# Pure_ADSR.net
KiCad netlist of a schematic drawn in EAGLE
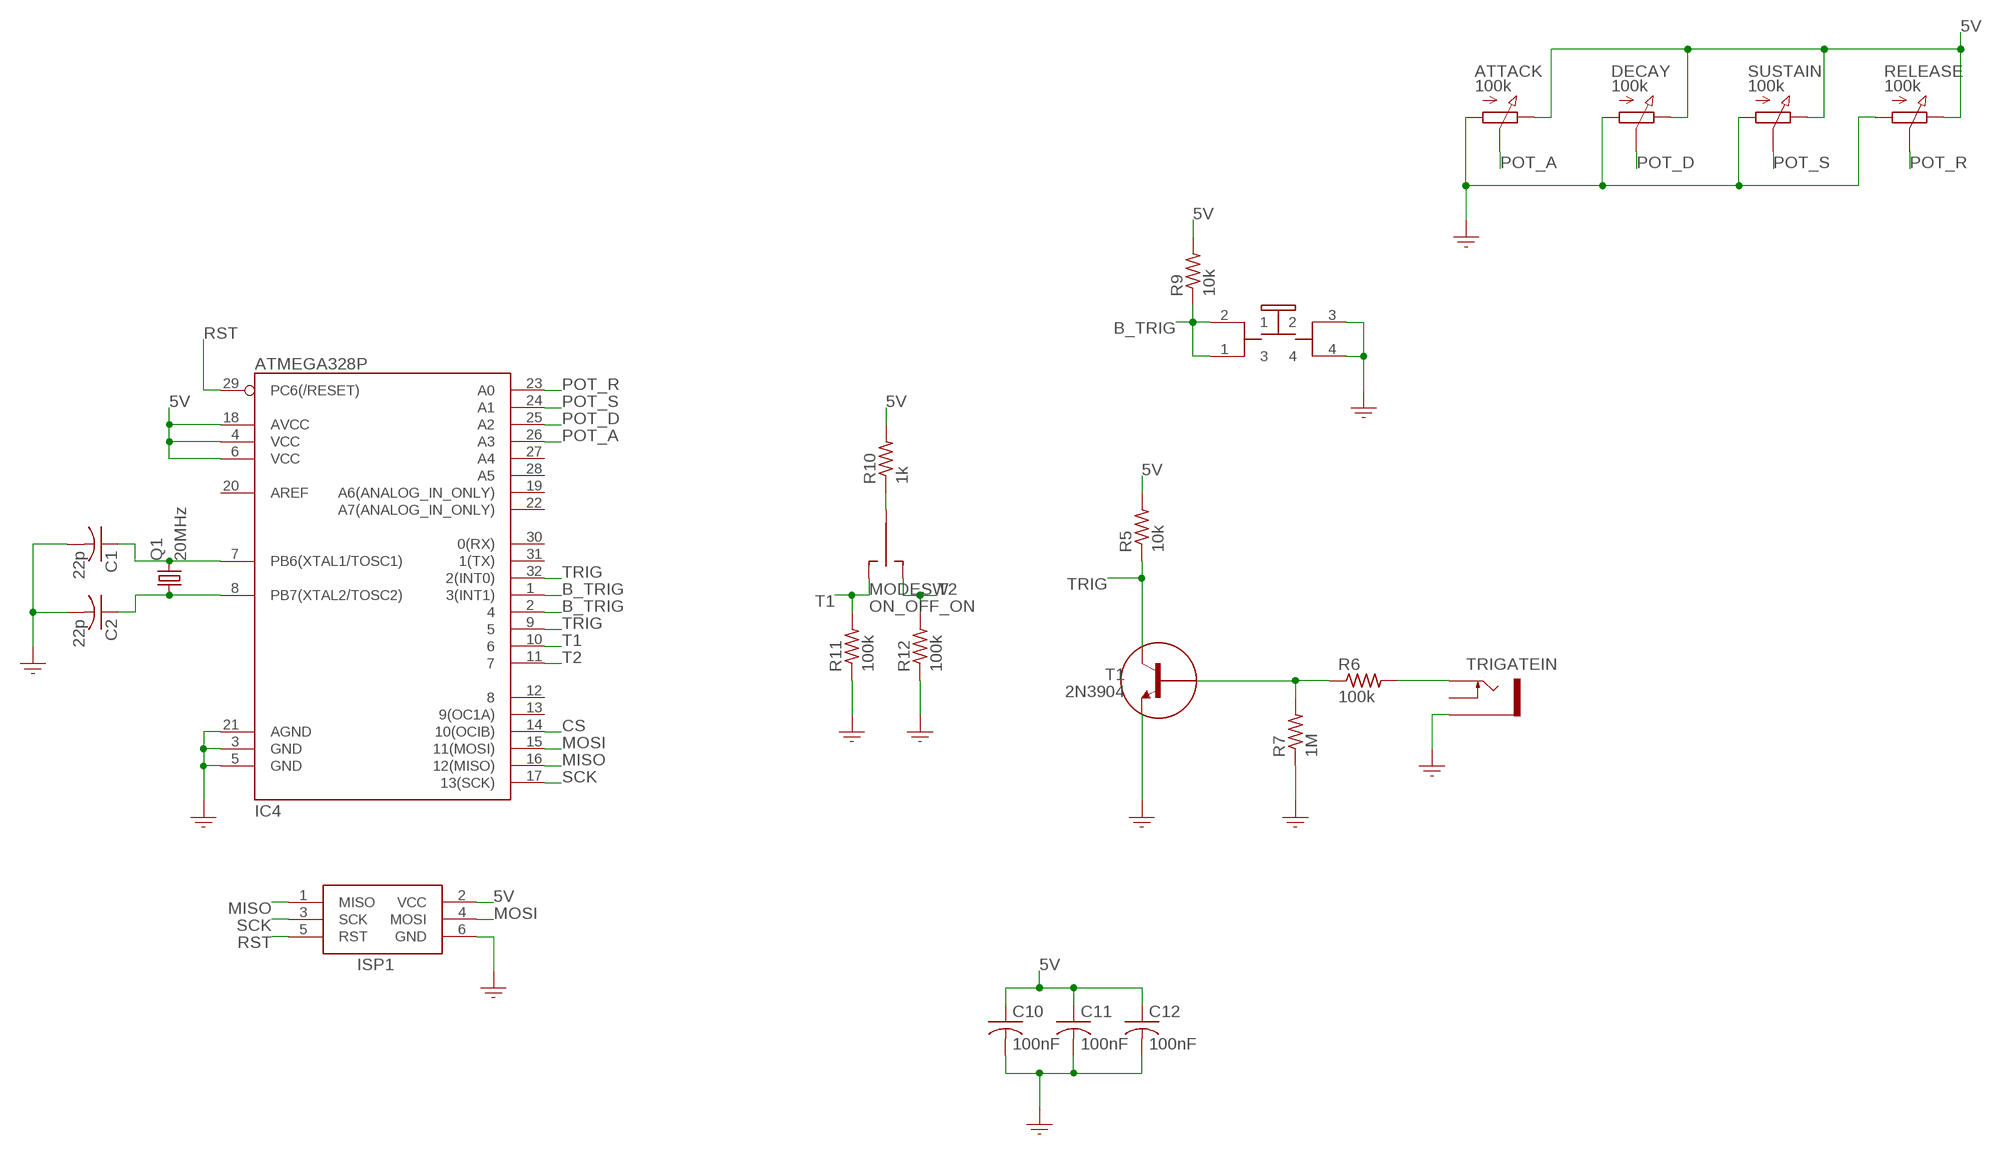
[diagram p0: schematic, sheet 1]
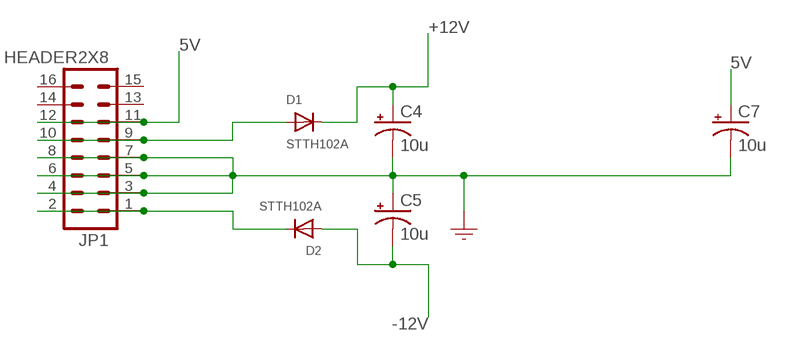
[diagram p1: schematic, sheet 2]
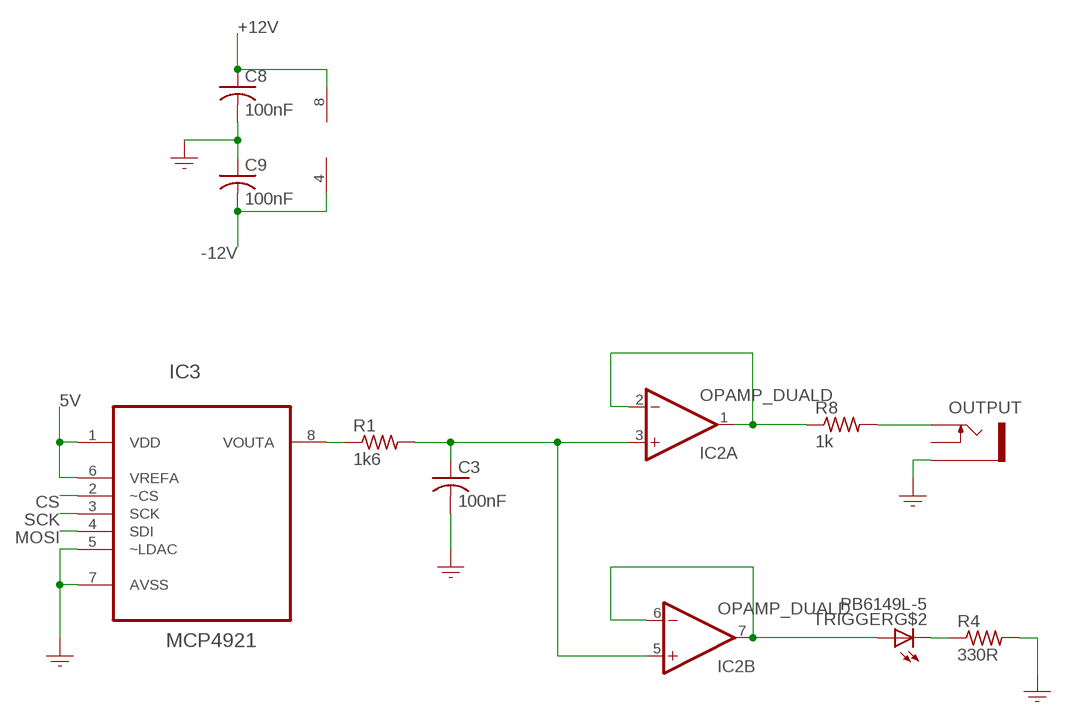
[diagram p2: schematic, sheet 3]

(export (version "E")
  (design (tool "Eeschema 10.0.6"))
  (components
    (comp (ref "ATTACK")
      (value "100k")
      (footprint "eagle-import:POTENTIOMETER_9MM")
      (libsource (lib "eagle-import") (part "RESISTOR_VARIABLE9MM_POT"))
    )
    (comp (ref "C1")
      (value "22p")
      (footprint "eagle-import:C0805")
      (libsource (lib "eagle-import") (part "CAPACITOR-USC0805"))
    )
    (comp (ref "C2")
      (value "22p")
      (footprint "eagle-import:C0805")
      (libsource (lib "eagle-import") (part "CAPACITOR-USC0805"))
    )
    (comp (ref "C10")
      (value "100nF")
      (footprint "eagle-import:C0805")
      (libsource (lib "eagle-import") (part "CAPACITOR-USC0805"))
    )
    (comp (ref "C11")
      (value "100nF")
      (footprint "eagle-import:C0805")
      (libsource (lib "eagle-import") (part "CAPACITOR-USC0805"))
    )
    (comp (ref "C12")
      (value "100nF")
      (footprint "eagle-import:C0805")
      (libsource (lib "eagle-import") (part "CAPACITOR-USC0805"))
    )
    (comp (ref "DECAY")
      (value "100k")
      (footprint "eagle-import:POTENTIOMETER_9MM")
      (libsource (lib "eagle-import") (part "RESISTOR_VARIABLE9MM_POT"))
    )
    (comp (ref "IC4")
      (value "ATMEGA328P")
      (footprint "eagle-import:TQFP32-08")
      (libsource (lib "eagle-import") (part "MICROPROCESSOR_ATMEGA328_SMT"))
    )
    (comp (ref "ISP1")
      (value "HEADER2X3-6")
      (footprint "eagle-import:AVRISP")
      (libsource (lib "eagle-import") (part "HEADER2X3-6"))
    )
    (comp (ref "MODESW")
      (value "ON_OFF_ON")
      (footprint "eagle-import:TOGGLE_SW")
      (libsource (lib "eagle-import") (part "SWITCH_TOGGLE_SPDT"))
    )
    (comp (ref "Q1")
      (value "20MHz")
      (footprint "eagle-import:HC49UP")
      (libsource (lib "eagle-import") (part "CRYSTALHC49UP"))
    )
    (comp (ref "R5")
      (value "10k")
      (footprint "eagle-import:R0805")
      (libsource (lib "eagle-import") (part "RESISTOR_USR0805"))
    )
    (comp (ref "R6")
      (value "100k")
      (footprint "eagle-import:R0805")
      (libsource (lib "eagle-import") (part "RESISTOR_USR0805"))
    )
    (comp (ref "R7")
      (value "1M")
      (footprint "eagle-import:R0805")
      (libsource (lib "eagle-import") (part "RESISTOR_USR0805"))
    )
    (comp (ref "R9")
      (value "10k")
      (footprint "eagle-import:R0805")
      (libsource (lib "eagle-import") (part "RESISTOR_USR0805"))
    )
    (comp (ref "R10")
      (value "1k")
      (footprint "eagle-import:R0805")
      (libsource (lib "eagle-import") (part "RESISTOR_USR0805"))
    )
    (comp (ref "R11")
      (value "100k")
      (footprint "eagle-import:R0805")
      (libsource (lib "eagle-import") (part "RESISTOR_USR0805"))
    )
    (comp (ref "R12")
      (value "100k")
      (footprint "eagle-import:R0805")
      (libsource (lib "eagle-import") (part "RESISTOR_USR0805"))
    )
    (comp (ref "RELEASE")
      (value "100k")
      (footprint "eagle-import:POTENTIOMETER_9MM")
      (libsource (lib "eagle-import") (part "RESISTOR_VARIABLE9MM_POT"))
    )
    (comp (ref "SUSTAIN")
      (value "100k")
      (footprint "eagle-import:POTENTIOMETER_9MM")
      (libsource (lib "eagle-import") (part "RESISTOR_VARIABLE9MM_POT"))
    )
    (comp (ref "T1")
      (value "2N3904")
      (footprint "eagle-import:SOT23")
      (libsource (lib "eagle-import") (part "TRANSISTOR_NPNMMBT2222A"))
    )
    (comp (ref "TRIGATEIN")
      (value "SOCKET_MONO_3.5MMPJ301M-12")
      (footprint "eagle-import:PJ301M-12")
      (libsource (lib "eagle-import") (part "SOCKET_MONO_3.5MMPJ301M-12"))
    )
    (comp (ref "TRIGGER")
      (value "PB6149L-5")
      (footprint "eagle-import:PB6149L")
      (libsource (lib "eagle-import") (part "SWITCH_PUSHBUTTON_LED"))
    )
    (comp (ref "C4")
      (value "10u")
      (footprint "eagle-import:153CLV-0505")
      (libsource (lib "eagle-import") (part "CAPACITOR_POL-US153CLV-0505"))
    )
    (comp (ref "C5")
      (value "10u")
      (footprint "eagle-import:153CLV-0505")
      (libsource (lib "eagle-import") (part "CAPACITOR_POL-US153CLV-0505"))
    )
    (comp (ref "C7")
      (value "10u")
      (footprint "eagle-import:153CLV-0505")
      (libsource (lib "eagle-import") (part "CAPACITOR_POL-US153CLV-0505"))
    )
    (comp (ref "D1")
      (value "STTH102A")
      (footprint "eagle-import:SMADIODE")
      (libsource (lib "eagle-import") (part "DIODESMA"))
    )
    (comp (ref "D2")
      (value "STTH102A")
      (footprint "eagle-import:SMADIODE")
      (libsource (lib "eagle-import") (part "DIODESMA"))
    )
    (comp (ref "JP1")
      (value "HEADER2X8")
      (footprint "eagle-import:POWER_SHROUDED")
      (libsource (lib "eagle-import") (part "HEADER2X8"))
    )
    (comp (ref "C3")
      (value "100nF")
      (footprint "eagle-import:C0805")
      (libsource (lib "eagle-import") (part "CAPACITOR-USC0805"))
    )
    (comp (ref "C8")
      (value "100nF")
      (footprint "eagle-import:C0805")
      (libsource (lib "eagle-import") (part "CAPACITOR-USC0805"))
    )
    (comp (ref "C9")
      (value "100nF")
      (footprint "eagle-import:C0805")
      (libsource (lib "eagle-import") (part "CAPACITOR-USC0805"))
    )
    (comp (ref "IC2")
      (value "OPAMP_DUALD")
      (footprint "eagle-import:SO08")
      (libsource (lib "eagle-import") (part "OPAMP_DUALD"))
    )
    (comp (ref "IC3")
      (value "MCP4921")
      (footprint "eagle-import:SOIC8")
      (libsource (lib "eagle-import") (part "DAC_SINGLE_12B_MCP4921"))
    )
    (comp (ref "OUTPUT")
      (value "SOCKET_MONO_3.5MMPJ301M-12")
      (footprint "eagle-import:PJ301M-12")
      (libsource (lib "eagle-import") (part "SOCKET_MONO_3.5MMPJ301M-12"))
    )
    (comp (ref "R1")
      (value "1k6")
      (footprint "eagle-import:R0805")
      (libsource (lib "eagle-import") (part "RESISTOR_USR0805"))
    )
    (comp (ref "R4")
      (value "330R")
      (footprint "eagle-import:R0805")
      (libsource (lib "eagle-import") (part "RESISTOR_USR0805"))
    )
    (comp (ref "R8")
      (value "1k")
      (footprint "eagle-import:R0805")
      (libsource (lib "eagle-import") (part "RESISTOR_USR0805"))
    )
  )
  (nets
    (net (code "1") (name "+12V") (class "Default")
      (node (ref "C4") (pin "+") (pinfunction "+_+") (pintype "passive"))
      (node (ref "C8") (pin "1") (pinfunction "1_1") (pintype "passive"))
      (node (ref "D1") (pin "C") (pinfunction "C_C") (pintype "passive"))
      (node (ref "IC2") (pin "8") (pinfunction "V+_8") (pintype "power_in"))
    )
    (net (code "2") (name "-12V") (class "Default")
      (node (ref "C5") (pin "-") (pinfunction "-_-") (pintype "passive"))
      (node (ref "C9") (pin "2") (pinfunction "2_2") (pintype "passive"))
      (node (ref "D2") (pin "A") (pinfunction "A_A") (pintype "passive"))
      (node (ref "IC2") (pin "4") (pinfunction "V-_4") (pintype "power_in"))
    )
    (net (code "3") (name "5V") (class "Default")
      (node (ref "ATTACK") (pin "P$3") (pinfunction "3_P$3") (pintype "passive"))
      (node (ref "C10") (pin "1") (pinfunction "1_1") (pintype "passive"))
      (node (ref "C11") (pin "1") (pinfunction "1_1") (pintype "passive"))
      (node (ref "C12") (pin "1") (pinfunction "1_1") (pintype "passive"))
      (node (ref "C7") (pin "+") (pinfunction "+_+") (pintype "passive"))
      (node (ref "DECAY") (pin "P$3") (pinfunction "3_P$3") (pintype "passive"))
      (node (ref "IC3") (pin "1") (pinfunction "VDD_1") (pintype "power_in"))
      (node (ref "IC3") (pin "6") (pinfunction "VREFA_6") (pintype "input"))
      (node (ref "IC4") (pin "18") (pinfunction "AVCC_18") (pintype "bidirectional"))
      (node (ref "IC4") (pin "4") (pinfunction "VCC_4") (pintype "bidirectional"))
      (node (ref "IC4") (pin "6") (pinfunction "VCC_6") (pintype "bidirectional"))
      (node (ref "ISP1") (pin "2") (pinfunction "VCC_2") (pintype "power_in"))
      (node (ref "JP1") (pin "11") (pinfunction "11_11") (pintype "passive"))
      (node (ref "JP1") (pin "12") (pinfunction "12_12") (pintype "passive"))
      (node (ref "R10") (pin "2") (pinfunction "2_2") (pintype "passive"))
      (node (ref "R5") (pin "2") (pinfunction "2_2") (pintype "passive"))
      (node (ref "R9") (pin "2") (pinfunction "2_2") (pintype "passive"))
      (node (ref "RELEASE") (pin "P$3") (pinfunction "3_P$3") (pintype "passive"))
      (node (ref "SUSTAIN") (pin "P$3") (pinfunction "3_P$3") (pintype "passive"))
    )
    (net (code "4") (name "B_TRIG") (class "Default")
      (node (ref "IC4") (pin "1") (pinfunction "3(INT1)_1") (pintype "bidirectional"))
      (node (ref "IC4") (pin "2") (pinfunction "4_2") (pintype "bidirectional"))
      (node (ref "R9") (pin "1") (pinfunction "1_1") (pintype "passive"))
      (node (ref "TRIGGER") (pin "1") (pinfunction "3_1") (pintype "bidirectional"))
      (node (ref "TRIGGER") (pin "2") (pinfunction "1_2") (pintype "bidirectional"))
    )
    (net (code "5") (name "CS") (class "Default")
      (node (ref "IC3") (pin "2") (pinfunction "~{CS}_2") (pintype "input"))
      (node (ref "IC4") (pin "14") (pinfunction "10(OCIB)_14") (pintype "bidirectional"))
    )
    (net (code "6") (name "GND") (class "Default")
      (node (ref "ATTACK") (pin "P$1") (pinfunction "1_P$1") (pintype "passive"))
      (node (ref "C1") (pin "2") (pinfunction "2_2") (pintype "passive"))
      (node (ref "C10") (pin "2") (pinfunction "2_2") (pintype "passive"))
      (node (ref "C11") (pin "2") (pinfunction "2_2") (pintype "passive"))
      (node (ref "C12") (pin "2") (pinfunction "2_2") (pintype "passive"))
      (node (ref "C2") (pin "2") (pinfunction "2_2") (pintype "passive"))
      (node (ref "C3") (pin "2") (pinfunction "2_2") (pintype "passive"))
      (node (ref "C4") (pin "-") (pinfunction "-_-") (pintype "passive"))
      (node (ref "C5") (pin "+") (pinfunction "+_+") (pintype "passive"))
      (node (ref "C7") (pin "-") (pinfunction "-_-") (pintype "passive"))
      (node (ref "C8") (pin "2") (pinfunction "2_2") (pintype "passive"))
      (node (ref "C9") (pin "1") (pinfunction "1_1") (pintype "passive"))
      (node (ref "DECAY") (pin "P$1") (pinfunction "1_P$1") (pintype "passive"))
      (node (ref "IC3") (pin "5") (pinfunction "~{LDAC}_5") (pintype "input"))
      (node (ref "IC3") (pin "7") (pinfunction "AVSS_7") (pintype "passive"))
      (node (ref "IC4") (pin "21") (pinfunction "AGND_21") (pintype "bidirectional"))
      (node (ref "IC4") (pin "3") (pinfunction "GND_3") (pintype "bidirectional"))
      (node (ref "IC4") (pin "5") (pinfunction "GND_5") (pintype "bidirectional"))
      (node (ref "ISP1") (pin "6") (pinfunction "GND_6") (pintype "power_in"))
      (node (ref "JP1") (pin "3") (pinfunction "3_3") (pintype "passive"))
      (node (ref "JP1") (pin "4") (pinfunction "4_4") (pintype "passive"))
      (node (ref "JP1") (pin "5") (pinfunction "5_5") (pintype "passive"))
      (node (ref "JP1") (pin "6") (pinfunction "6_6") (pintype "passive"))
      (node (ref "JP1") (pin "7") (pinfunction "7_7") (pintype "passive"))
      (node (ref "JP1") (pin "8") (pinfunction "8_8") (pintype "passive"))
      (node (ref "OUTPUT") (pin "GND") (pinfunction "SLEEVE_GND") (pintype "passive"))
      (node (ref "R11") (pin "1") (pinfunction "1_1") (pintype "passive"))
      (node (ref "R12") (pin "1") (pinfunction "1_1") (pintype "passive"))
      (node (ref "R4") (pin "2") (pinfunction "2_2") (pintype "passive"))
      (node (ref "R7") (pin "1") (pinfunction "1_1") (pintype "passive"))
      (node (ref "RELEASE") (pin "P$1") (pinfunction "1_P$1") (pintype "passive"))
      (node (ref "SUSTAIN") (pin "P$1") (pinfunction "1_P$1") (pintype "passive"))
      (node (ref "T1") (pin "2") (pinfunction "E_2") (pintype "passive"))
      (node (ref "TRIGATEIN") (pin "GND") (pinfunction "SLEEVE_GND") (pintype "passive"))
      (node (ref "TRIGGER") (pin "3") (pinfunction "2_3") (pintype "bidirectional"))
      (node (ref "TRIGGER") (pin "4") (pinfunction "4_4") (pintype "bidirectional"))
    )
    (net (code "7") (name "MISO") (class "Default")
      (node (ref "IC4") (pin "16") (pinfunction "12(MISO)_16") (pintype "bidirectional"))
      (node (ref "ISP1") (pin "1") (pinfunction "MISO_1") (pintype "input"))
    )
    (net (code "8") (name "MOSI") (class "Default")
      (node (ref "IC3") (pin "4") (pinfunction "SDI_4") (pintype "input"))
      (node (ref "IC4") (pin "15") (pinfunction "11(MOSI)_15") (pintype "bidirectional"))
      (node (ref "ISP1") (pin "4") (pinfunction "MOSI_4") (pintype "output"))
    )
    (net (code "9") (name "Net-(D1-PadA)") (class "Default")
      (node (ref "D1") (pin "A") (pinfunction "A_A") (pintype "passive"))
      (node (ref "JP1") (pin "10") (pinfunction "10_10") (pintype "passive"))
      (node (ref "JP1") (pin "9") (pinfunction "9_9") (pintype "passive"))
    )
    (net (code "10") (name "Net-(D2-PadC)") (class "Default")
      (node (ref "D2") (pin "C") (pinfunction "C_C") (pintype "passive"))
      (node (ref "JP1") (pin "1") (pinfunction "1_1") (pintype "passive"))
      (node (ref "JP1") (pin "2") (pinfunction "2_2") (pintype "passive"))
    )
    (net (code "11") (name "Net-(IC2A-+IN)") (class "Default")
      (node (ref "C3") (pin "1") (pinfunction "1_1") (pintype "passive"))
      (node (ref "IC2") (pin "3") (pinfunction "+IN_3") (pintype "input"))
      (node (ref "IC2") (pin "5") (pinfunction "+IN_5") (pintype "input"))
      (node (ref "R1") (pin "2") (pinfunction "2_2") (pintype "passive"))
    )
    (net (code "12") (name "Net-(IC2A--IN)") (class "Default")
      (node (ref "IC2") (pin "1") (pinfunction "OUT_1") (pintype "output"))
      (node (ref "IC2") (pin "2") (pinfunction "-IN_2") (pintype "input"))
      (node (ref "R8") (pin "1") (pinfunction "1_1") (pintype "passive"))
    )
    (net (code "13") (name "Net-(IC2B--IN)") (class "Default")
      (node (ref "IC2") (pin "6") (pinfunction "-IN_6") (pintype "input"))
      (node (ref "IC2") (pin "7") (pinfunction "OUT_7") (pintype "output"))
      (node (ref "TRIGGER") (pin "A") (pinfunction "A_A") (pintype "passive"))
    )
    (net (code "14") (name "Net-(IC3-VOUTA)") (class "Default")
      (node (ref "IC3") (pin "8") (pinfunction "VOUTA_8") (pintype "output"))
      (node (ref "R1") (pin "1") (pinfunction "1_1") (pintype "passive"))
    )
    (net (code "15") (name "Net-(IC4-PB6(XTAL1{slash}TOSC1))") (class "Default")
      (node (ref "C1") (pin "1") (pinfunction "1_1") (pintype "passive"))
      (node (ref "IC4") (pin "7") (pinfunction "PB6(XTAL1/TOSC1)_7") (pintype "bidirectional"))
      (node (ref "Q1") (pin "2") (pinfunction "2_2") (pintype "passive"))
    )
    (net (code "16") (name "Net-(IC4-PB7(XTAL2{slash}TOSC2))") (class "Default")
      (node (ref "C2") (pin "1") (pinfunction "1_1") (pintype "passive"))
      (node (ref "IC4") (pin "8") (pinfunction "PB7(XTAL2/TOSC2)_8") (pintype "bidirectional"))
      (node (ref "Q1") (pin "1") (pinfunction "1_1") (pintype "passive"))
    )
    (net (code "17") (name "Net-(MODESW-P)") (class "Default")
      (node (ref "MODESW") (pin "2") (pinfunction "P_2") (pintype "passive"))
      (node (ref "R10") (pin "1") (pinfunction "1_1") (pintype "passive"))
    )
    (net (code "18") (name "Net-(OUTPUT-PadTIP)") (class "Default")
      (node (ref "OUTPUT") (pin "TIP") (pinfunction "TIP_TIP") (pintype "passive"))
      (node (ref "R8") (pin "2") (pinfunction "2_2") (pintype "passive"))
    )
    (net (code "19") (name "Net-(R6-Pad2)") (class "Default")
      (node (ref "R6") (pin "2") (pinfunction "2_2") (pintype "passive"))
      (node (ref "TRIGATEIN") (pin "TIP") (pinfunction "TIP_TIP") (pintype "passive"))
    )
    (net (code "20") (name "Net-(T1-B)") (class "Default")
      (node (ref "R6") (pin "1") (pinfunction "1_1") (pintype "passive"))
      (node (ref "R7") (pin "2") (pinfunction "2_2") (pintype "passive"))
      (node (ref "T1") (pin "1") (pinfunction "B_1") (pintype "passive"))
    )
    (net (code "21") (name "Net-(TRIGGERB-C)") (class "Default")
      (node (ref "R4") (pin "1") (pinfunction "1_1") (pintype "passive"))
      (node (ref "TRIGGER") (pin "K") (pinfunction "C_K") (pintype "passive"))
    )
    (net (code "22") (name "POT_A") (class "Default")
      (node (ref "ATTACK") (pin "P$2") (pinfunction "2_P$2") (pintype "passive"))
      (node (ref "IC4") (pin "26") (pinfunction "A3_26") (pintype "bidirectional"))
    )
    (net (code "23") (name "POT_D") (class "Default")
      (node (ref "DECAY") (pin "P$2") (pinfunction "2_P$2") (pintype "passive"))
      (node (ref "IC4") (pin "25") (pinfunction "A2_25") (pintype "bidirectional"))
    )
    (net (code "24") (name "POT_R") (class "Default")
      (node (ref "IC4") (pin "23") (pinfunction "A0_23") (pintype "bidirectional"))
      (node (ref "RELEASE") (pin "P$2") (pinfunction "2_P$2") (pintype "passive"))
    )
    (net (code "25") (name "POT_S") (class "Default")
      (node (ref "IC4") (pin "24") (pinfunction "A1_24") (pintype "bidirectional"))
      (node (ref "SUSTAIN") (pin "P$2") (pinfunction "2_P$2") (pintype "passive"))
    )
    (net (code "26") (name "RST") (class "Default")
      (node (ref "IC4") (pin "29") (pinfunction "PC6(/RESET)_29") (pintype "bidirectional"))
      (node (ref "ISP1") (pin "5") (pinfunction "RST_5") (pintype "output"))
    )
    (net (code "27") (name "SCK") (class "Default")
      (node (ref "IC3") (pin "3") (pinfunction "SCK_3") (pintype "input"))
      (node (ref "IC4") (pin "17") (pinfunction "13(SCK)_17") (pintype "bidirectional"))
      (node (ref "ISP1") (pin "3") (pinfunction "SCK_3") (pintype "output"))
    )
    (net (code "28") (name "T1") (class "Default")
      (node (ref "IC4") (pin "10") (pinfunction "6_10") (pintype "bidirectional"))
      (node (ref "MODESW") (pin "3") (pinfunction "S_3") (pintype "passive"))
      (node (ref "R11") (pin "2") (pinfunction "2_2") (pintype "passive"))
    )
    (net (code "29") (name "T2") (class "Default")
      (node (ref "IC4") (pin "11") (pinfunction "7_11") (pintype "bidirectional"))
      (node (ref "MODESW") (pin "1") (pinfunction "O_1") (pintype "passive"))
      (node (ref "R12") (pin "2") (pinfunction "2_2") (pintype "passive"))
    )
    (net (code "30") (name "TRIG") (class "Default")
      (node (ref "IC4") (pin "32") (pinfunction "2(INT0)_32") (pintype "bidirectional"))
      (node (ref "IC4") (pin "9") (pinfunction "5_9") (pintype "bidirectional"))
      (node (ref "R5") (pin "1") (pinfunction "1_1") (pintype "passive"))
      (node (ref "T1") (pin "3") (pinfunction "C_3") (pintype "passive"))
    )
    (net (code "31") (name "unconnected-(IC4-0(RX)-Pad30)") (class "Default")
      (node (ref "IC4") (pin "30") (pinfunction "0(RX)_30") (pintype "bidirectional"))
    )
    (net (code "32") (name "unconnected-(IC4-1(TX)-Pad31)") (class "Default")
      (node (ref "IC4") (pin "31") (pinfunction "1(TX)_31") (pintype "bidirectional"))
    )
    (net (code "33") (name "unconnected-(IC4-8-Pad12)") (class "Default")
      (node (ref "IC4") (pin "12") (pinfunction "8_12") (pintype "bidirectional"))
    )
    (net (code "34") (name "unconnected-(IC4-9(OC1A)-Pad13)") (class "Default")
      (node (ref "IC4") (pin "13") (pinfunction "9(OC1A)_13") (pintype "bidirectional"))
    )
    (net (code "35") (name "unconnected-(IC4-A4-Pad27)") (class "Default")
      (node (ref "IC4") (pin "27") (pinfunction "A4_27") (pintype "bidirectional"))
    )
    (net (code "36") (name "unconnected-(IC4-A5-Pad28)") (class "Default")
      (node (ref "IC4") (pin "28") (pinfunction "A5_28") (pintype "bidirectional"))
    )
    (net (code "37") (name "unconnected-(IC4-A6(ANALOG_IN_ONLY)-Pad19)") (class "Default")
      (node (ref "IC4") (pin "19") (pinfunction "A6(ANALOG_IN_ONLY)_19") (pintype "bidirectional"))
    )
    (net (code "38") (name "unconnected-(IC4-A7(ANALOG_IN_ONLY)-Pad22)") (class "Default")
      (node (ref "IC4") (pin "22") (pinfunction "A7(ANALOG_IN_ONLY)_22") (pintype "bidirectional"))
    )
    (net (code "39") (name "unconnected-(IC4-AREF-Pad20)") (class "Default")
      (node (ref "IC4") (pin "20") (pinfunction "AREF_20") (pintype "bidirectional"))
    )
    (net (code "40") (name "unconnected-(JP1-Pad13)") (class "Default")
      (node (ref "JP1") (pin "13") (pinfunction "13_13") (pintype "passive"))
    )
    (net (code "41") (name "unconnected-(JP1-Pad14)") (class "Default")
      (node (ref "JP1") (pin "14") (pinfunction "14_14") (pintype "passive"))
    )
    (net (code "42") (name "unconnected-(JP1-Pad15)") (class "Default")
      (node (ref "JP1") (pin "15") (pinfunction "15_15") (pintype "passive"))
    )
    (net (code "43") (name "unconnected-(JP1-Pad16)") (class "Default")
      (node (ref "JP1") (pin "16") (pinfunction "16_16") (pintype "passive"))
    )
    (net (code "44") (name "unconnected-(OUTPUT-SWITCH-PadNORM)") (class "Default")
      (node (ref "OUTPUT") (pin "NORM") (pinfunction "SWITCH_NORM") (pintype "passive"))
    )
    (net (code "45") (name "unconnected-(TRIGATEIN-SWITCH-PadNORM)") (class "Default")
      (node (ref "TRIGATEIN") (pin "NORM") (pinfunction "SWITCH_NORM") (pintype "passive"))
    )
  )
)
